# ESP32.net
KiCad netlist of a schematic drawn in EAGLE
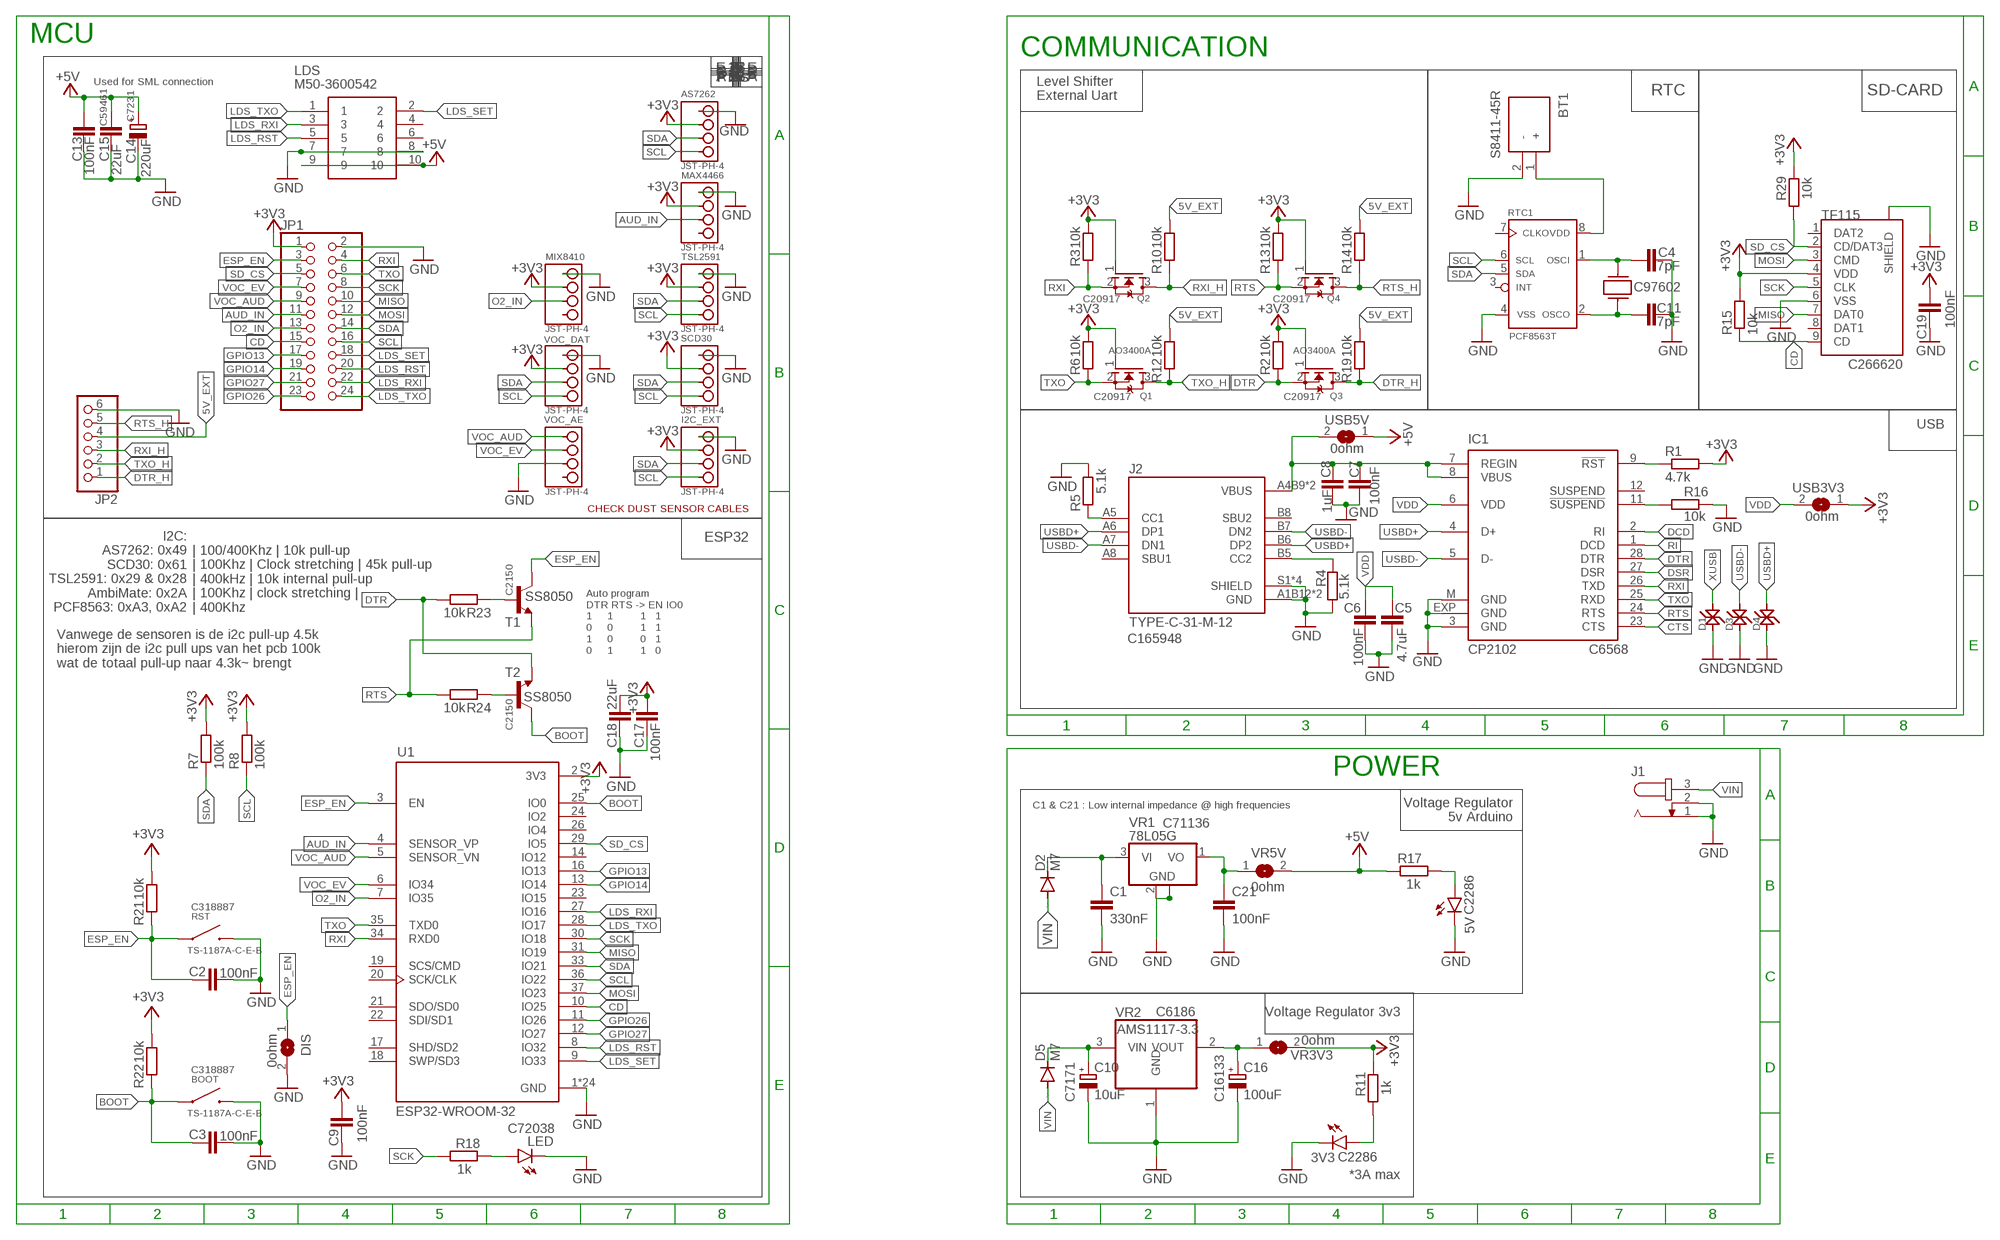
[diagram p0: schematic, sheet 1]

(export (version "E")
  (design (tool "Eeschema 10.0.6"))
  (components
    (comp (ref "3V3")
      (value "C2286")
      (footprint "eagle-import:CHIPLED_0603")
      (fields (field (name "PTNR") "C2286"))
      (libsource (lib "eagle-import") (part "LEDCHIPLED_0603"))
    )
    (comp (ref "5V")
      (value "C2286")
      (footprint "eagle-import:CHIPLED_0603")
      (fields (field (name "PTNR") "C2286"))
      (libsource (lib "eagle-import") (part "LEDCHIPLED_0603"))
    )
    (comp (ref "AS7262")
      (value "JST-PH-4")
      (footprint "eagle-import:JST-PH-4")
      (libsource (lib "eagle-import") (part "JST-PH-4"))
    )
    (comp (ref "BOOT")
      (value "TS-1187A-C-E-B")
      (footprint "eagle-import:TS-1187A-C-E-B")
      (fields (field (name "PRTNR") "C318887"))
      (libsource (lib "eagle-import") (part "TS-1187A-C-E-B"))
    )
    (comp (ref "BT1")
      (value "S8411-45R")
      (footprint "eagle-import:S8411-45R_1")
      (fields (field (name "MOUSER_PART_NUMBER") "855-S8411-45R"))
      (libsource (lib "eagle-import") (part "S8411-45R"))
    )
    (comp (ref "C1")
      (value "330nF")
      (footprint "eagle-import:C0805")
      (libsource (lib "eagle-import") (part "C-EUC0805"))
    )
    (comp (ref "C2")
      (value "100nF")
      (footprint "eagle-import:C0402")
      (libsource (lib "eagle-import") (part "C-EUC0402"))
    )
    (comp (ref "C3")
      (value "100nF")
      (footprint "eagle-import:C0402")
      (libsource (lib "eagle-import") (part "C-EUC0402"))
    )
    (comp (ref "C4")
      (value "7pF")
      (footprint "eagle-import:C0402")
      (libsource (lib "eagle-import") (part "C-EUC0402"))
    )
    (comp (ref "C5")
      (value "4.7uF")
      (footprint "eagle-import:C0402")
      (libsource (lib "eagle-import") (part "C-EUC0402"))
    )
    (comp (ref "C6")
      (value "100nF")
      (footprint "eagle-import:C0402")
      (libsource (lib "eagle-import") (part "C-EUC0402"))
    )
    (comp (ref "C7")
      (value "100nF")
      (footprint "eagle-import:C0402")
      (libsource (lib "eagle-import") (part "C-EUC0402"))
    )
    (comp (ref "C8")
      (value "1uF")
      (footprint "eagle-import:C0402")
      (libsource (lib "eagle-import") (part "C-EUC0402"))
    )
    (comp (ref "C9")
      (value "100nF")
      (footprint "eagle-import:C0402")
      (libsource (lib "eagle-import") (part "C-EUC0402"))
    )
    (comp (ref "C10")
      (value "10uF")
      (footprint "eagle-import:A_3216-18R")
      (fields (field (name "PTRNR") "C7171"))
      (libsource (lib "eagle-import") (part "CPOL-EUA/3216-18R"))
    )
    (comp (ref "C11")
      (value "7pF")
      (footprint "eagle-import:C0402")
      (libsource (lib "eagle-import") (part "C-EUC0402"))
    )
    (comp (ref "C13")
      (value "100nF")
      (footprint "eagle-import:C0402")
      (libsource (lib "eagle-import") (part "C-EUC0402"))
    )
    (comp (ref "C14")
      (value "220uF")
      (footprint "eagle-import:D_7343-31R")
      (fields (field (name "PTRNR") "C7231"))
      (libsource (lib "eagle-import") (part "CPOL-EUD/7343-31R"))
    )
    (comp (ref "C15")
      (value "22uF")
      (footprint "eagle-import:C0603")
      (fields (field (name "PTRNR") "C59461"))
      (libsource (lib "eagle-import") (part "C-EUC0603"))
    )
    (comp (ref "C16")
      (value "100uF")
      (footprint "eagle-import:B_3528-21W")
      (fields (field (name "PTRNR") "C16133"))
      (libsource (lib "eagle-import") (part "CPOL-EUB/3528-21W"))
    )
    (comp (ref "C17")
      (value "100nF")
      (footprint "eagle-import:C0402")
      (libsource (lib "eagle-import") (part "C-EUC0402"))
    )
    (comp (ref "C18")
      (value "22uF")
      (footprint "eagle-import:C0603")
      (libsource (lib "eagle-import") (part "C-EUC0603"))
    )
    (comp (ref "C19")
      (value "100nF")
      (footprint "eagle-import:C0402")
      (libsource (lib "eagle-import") (part "C-EUC0402"))
    )
    (comp (ref "C21")
      (value "100nF")
      (footprint "eagle-import:C0402")
      (libsource (lib "eagle-import") (part "C-EUC0402"))
    )
    (comp (ref "D1")
      (value "LESD5D5.0CT1G")
      (footprint "eagle-import:LESD5D5.0CT1G")
      (libsource (lib "eagle-import") (part "LESD5D5.0CT1G"))
    )
    (comp (ref "D2")
      (value "M7")
      (footprint "eagle-import:DO-214AC")
      (libsource (lib "eagle-import") (part "M7DO-214AC"))
    )
    (comp (ref "D3")
      (value "LESD5D5.0CT1G")
      (footprint "eagle-import:LESD5D5.0CT1G")
      (libsource (lib "eagle-import") (part "LESD5D5.0CT1G"))
    )
    (comp (ref "D4")
      (value "LESD5D5.0CT1G")
      (footprint "eagle-import:LESD5D5.0CT1G")
      (libsource (lib "eagle-import") (part "LESD5D5.0CT1G"))
    )
    (comp (ref "D5")
      (value "M7")
      (footprint "eagle-import:DO-214AC")
      (libsource (lib "eagle-import") (part "M7DO-214AC"))
    )
    (comp (ref "DIS")
      (value "0ohm")
      (footprint "eagle-import:SJ")
      (libsource (lib "eagle-import") (part "SJ"))
    )
    (comp (ref "G1")
      (value "32.768KHZ")
      (footprint "eagle-import:32.768KHZ")
      (fields (field (name "PTRNR") "C97602"))
      (libsource (lib "eagle-import") (part "32.768KHZ"))
    )
    (comp (ref "I2C_EXT")
      (value "JST-PH-4")
      (footprint "eagle-import:JST-PH-4")
      (libsource (lib "eagle-import") (part "JST-PH-4"))
    )
    (comp (ref "IC1")
      (value "CP2102")
      (footprint "eagle-import:MLP28")
      (fields
        (field (name "MF") "FARNELL")
        (field (name "MPN") "CP2102-GM")
        (field (name "PTRNR") "C6568")
        (field (name "PTRNR_1") "C6568")
      )
      (libsource (lib "eagle-import") (part "CP2102"))
    )
    (comp (ref "J1")
      (value "JACK-PLUG1")
      (footprint "eagle-import:SPC4078")
      (libsource (lib "eagle-import") (part "JACK-PLUG1"))
    )
    (comp (ref "J2")
      (value "TYPE-C-31-M-12")
      (footprint "eagle-import:HRO_TYPE-C-31-M-12")
      (fields
        (field (name "MF") "HRO Electronics Co., Ltd.")
        (field (name "PTRNR") "C165948")
        (field (name "PTRNR_1") "C165948")
      )
      (libsource (lib "eagle-import") (part "TYPE-C-31-M-12"))
    )
    (comp (ref "JP1")
      (value "PINHD-2X12")
      (footprint "eagle-import:2X12")
      (libsource (lib "eagle-import") (part "PINHD-2X12"))
    )
    (comp (ref "JP2")
      (value "PINHD-1X6/90")
      (footprint "eagle-import:1X06_90")
      (libsource (lib "eagle-import") (part "PINHD-1X6/90"))
    )
    (comp (ref "LDS")
      (value "M50-3600542")
      (footprint "eagle-import:M503600542")
      (fields (field (name "MOUSER_PART_NUMBER") "855-M50-3600542"))
      (libsource (lib "eagle-import") (part "M50-3600542"))
    )
    (comp (ref "LED")
      (value "YELLOW")
      (footprint "eagle-import:CHIPLED_0603")
      (fields (field (name "PTRNR") "C72038"))
      (libsource (lib "eagle-import") (part "LEDCHIPLED_0603"))
    )
    (comp (ref "MAX4466")
      (value "JST-PH-4")
      (footprint "eagle-import:JST-PH-4")
      (libsource (lib "eagle-import") (part "JST-PH-4"))
    )
    (comp (ref "MIX8410")
      (value "JST-PH-4")
      (footprint "eagle-import:JST-PH-4")
      (libsource (lib "eagle-import") (part "Tilmann_31608911_JST-PH-4"))
    )
    (comp (ref "Q1")
      (value "AO3400A")
      (footprint "eagle-import:SOT23")
      (fields (field (name "PTRNR") "C20917"))
      (libsource (lib "eagle-import") (part "MOSFET-NREFLOW"))
    )
    (comp (ref "Q2")
      (value "AO3400A")
      (footprint "eagle-import:SOT23")
      (fields (field (name "PTRNR") "C20917"))
      (libsource (lib "eagle-import") (part "MOSFET-NREFLOW"))
    )
    (comp (ref "Q3")
      (value "AO3400A")
      (footprint "eagle-import:SOT23")
      (fields (field (name "PTRNR") "C20917"))
      (libsource (lib "eagle-import") (part "MOSFET-NREFLOW"))
    )
    (comp (ref "Q4")
      (value "AO3400A")
      (footprint "eagle-import:SOT23")
      (fields (field (name "PTRNR") "C20917"))
      (libsource (lib "eagle-import") (part "MOSFET-NREFLOW"))
    )
    (comp (ref "R1")
      (value "4.7k")
      (footprint "eagle-import:R0402")
      (libsource (lib "eagle-import") (part "R-EU_R0402"))
    )
    (comp (ref "R2")
      (value "10k")
      (footprint "eagle-import:R0402")
      (libsource (lib "eagle-import") (part "R-EU_R0402"))
    )
    (comp (ref "R3")
      (value "10k")
      (footprint "eagle-import:R0402")
      (libsource (lib "eagle-import") (part "R-EU_R0402"))
    )
    (comp (ref "R4")
      (value "5.1k")
      (footprint "eagle-import:R0402")
      (libsource (lib "eagle-import") (part "R-EU_R0402"))
    )
    (comp (ref "R5")
      (value "5.1k")
      (footprint "eagle-import:R0402")
      (libsource (lib "eagle-import") (part "R-EU_R0402"))
    )
    (comp (ref "R6")
      (value "10k")
      (footprint "eagle-import:R0402")
      (libsource (lib "eagle-import") (part "R-EU_R0402"))
    )
    (comp (ref "R7")
      (value "100k")
      (footprint "eagle-import:R0402")
      (libsource (lib "eagle-import") (part "R-EU_R0402"))
    )
    (comp (ref "R8")
      (value "100k")
      (footprint "eagle-import:R0402")
      (libsource (lib "eagle-import") (part "R-EU_R0402"))
    )
    (comp (ref "R10")
      (value "10k")
      (footprint "eagle-import:R0402")
      (libsource (lib "eagle-import") (part "R-EU_R0402"))
    )
    (comp (ref "R11")
      (value "1k")
      (footprint "eagle-import:R0805")
      (libsource (lib "eagle-import") (part "R-EU_R0805"))
    )
    (comp (ref "R12")
      (value "10k")
      (footprint "eagle-import:R0402")
      (libsource (lib "eagle-import") (part "R-EU_R0402"))
    )
    (comp (ref "R13")
      (value "10k")
      (footprint "eagle-import:R0402")
      (libsource (lib "eagle-import") (part "R-EU_R0402"))
    )
    (comp (ref "R14")
      (value "10k")
      (footprint "eagle-import:R0402")
      (libsource (lib "eagle-import") (part "R-EU_R0402"))
    )
    (comp (ref "R15")
      (value "10k")
      (footprint "eagle-import:R0402")
      (libsource (lib "eagle-import") (part "R-EU_R0402"))
    )
    (comp (ref "R16")
      (value "10k")
      (footprint "eagle-import:R0402")
      (libsource (lib "eagle-import") (part "R-EU_R0402"))
    )
    (comp (ref "R17")
      (value "1k")
      (footprint "eagle-import:R0805")
      (libsource (lib "eagle-import") (part "R-EU_R0805"))
    )
    (comp (ref "R18")
      (value "1k")
      (footprint "eagle-import:R0805")
      (libsource (lib "eagle-import") (part "R-EU_R0805"))
    )
    (comp (ref "R19")
      (value "10k")
      (footprint "eagle-import:R0402")
      (libsource (lib "eagle-import") (part "R-EU_R0402"))
    )
    (comp (ref "R21")
      (value "10k")
      (footprint "eagle-import:R0402")
      (libsource (lib "eagle-import") (part "R-EU_R0402"))
    )
    (comp (ref "R22")
      (value "10k")
      (footprint "eagle-import:R0402")
      (libsource (lib "eagle-import") (part "R-EU_R0402"))
    )
    (comp (ref "R23")
      (value "10k")
      (footprint "eagle-import:R0402")
      (libsource (lib "eagle-import") (part "R-EU_R0402"))
    )
    (comp (ref "R24")
      (value "10k")
      (footprint "eagle-import:R0402")
      (libsource (lib "eagle-import") (part "R-EU_R0402"))
    )
    (comp (ref "R29")
      (value "10k")
      (footprint "eagle-import:R0402")
      (libsource (lib "eagle-import") (part "R-EU_R0402"))
    )
    (comp (ref "RST")
      (value "TS-1187A-C-E-B")
      (footprint "eagle-import:TS-1187A-C-E-B")
      (fields (field (name "PRTNR") "C318887"))
      (libsource (lib "eagle-import") (part "TS-1187A-C-E-B"))
    )
    (comp (ref "RTC1")
      (value "PCF8563T")
      (footprint "eagle-import:SOIC8")
      (libsource (lib "eagle-import") (part "PCF8563T"))
    )
    (comp (ref "SCD30")
      (value "JST-PH-4")
      (footprint "eagle-import:JST-PH-4")
      (libsource (lib "eagle-import") (part "JST-PH-4"))
    )
    (comp (ref "T1")
      (value "SS8050")
      (footprint "eagle-import:SOT23-BEC")
      (fields (field (name "PTNR") "C2150"))
      (libsource (lib "eagle-import") (part "-NPN-SOT23-BECBC808"))
    )
    (comp (ref "T2")
      (value "SS8050")
      (footprint "eagle-import:SOT23-BEC")
      (fields (field (name "PTNR") "C2150"))
      (libsource (lib "eagle-import") (part "-NPN-SOT23-BECBC808"))
    )
    (comp (ref "TF115")
      (value "TF-115")
      (footprint "eagle-import:TF-115")
      (fields (field (name "PTRNR") "C266620"))
      (libsource (lib "eagle-import") (part "TF-115"))
    )
    (comp (ref "TSL2591")
      (value "JST-PH-4")
      (footprint "eagle-import:JST-PH-4")
      (libsource (lib "eagle-import") (part "JST-PH-4"))
    )
    (comp (ref "U1")
      (value "ESP32-WROOM-32")
      (footprint "eagle-import:MODULE_ESP32-WROOM-32")
      (fields (field (name "MF") "Espressif Systems"))
      (libsource (lib "eagle-import") (part "ESP32-WROOM-32"))
    )
    (comp (ref "USB3V3")
      (value "0ohm")
      (footprint "eagle-import:SJ")
      (libsource (lib "eagle-import") (part "SJ"))
    )
    (comp (ref "USB5V")
      (value "0ohm")
      (footprint "eagle-import:SJ")
      (libsource (lib "eagle-import") (part "SJ"))
    )
    (comp (ref "VOC_AE")
      (value "JST-PH-4")
      (footprint "eagle-import:JST-PH-4")
      (libsource (lib "eagle-import") (part "JST-PH-4"))
    )
    (comp (ref "VOC_DAT")
      (value "JST-PH-4")
      (footprint "eagle-import:JST-PH-4")
      (libsource (lib "eagle-import") (part "JST-PH-4"))
    )
    (comp (ref "VR1")
      (value "78L05G")
      (footprint "eagle-import:SOT89")
      (fields (field (name "PTRNR") "C71136"))
      (libsource (lib "eagle-import") (part "78LF05"))
    )
    (comp (ref "VR2")
      (value "AMS1117-3.3")
      (footprint "eagle-import:SOT223")
      (fields (field (name "MPN") "REG1117") (field (name "PTNR") "C6186"))
      (libsource (lib "eagle-import") (part "REG1117"))
    )
    (comp (ref "VR3V3")
      (value "0ohm")
      (footprint "eagle-import:SJ")
      (libsource (lib "eagle-import") (part "SJ"))
    )
    (comp (ref "VR5V")
      (value "0ohm")
      (footprint "eagle-import:SJ")
      (libsource (lib "eagle-import") (part "SJ"))
    )
  )
  (nets
    (net (code "1") (name "+3V3") (class "Default")
      (node (ref "AS7262") (pin "P2") (pinfunction "2_P2") (pintype "bidirectional"))
      (node (ref "C17") (pin "2") (pinfunction "2_2") (pintype "passive"))
      (node (ref "C18") (pin "2") (pinfunction "2_2") (pintype "passive"))
      (node (ref "C19") (pin "2") (pinfunction "2_2") (pintype "passive"))
      (node (ref "C9") (pin "2") (pinfunction "2_2") (pintype "passive"))
      (node (ref "I2C_EXT") (pin "P2") (pinfunction "2_P2") (pintype "bidirectional"))
      (node (ref "JP1") (pin "1") (pinfunction "1_1") (pintype "passive"))
      (node (ref "MAX4466") (pin "P2") (pinfunction "2_P2") (pintype "bidirectional"))
      (node (ref "MIX8410") (pin "P2") (pinfunction "2_P2") (pintype "bidirectional"))
      (node (ref "Q1") (pin "1") (pinfunction "G_1") (pintype "bidirectional"))
      (node (ref "Q2") (pin "1") (pinfunction "G_1") (pintype "bidirectional"))
      (node (ref "Q3") (pin "1") (pinfunction "G_1") (pintype "bidirectional"))
      (node (ref "Q4") (pin "1") (pinfunction "G_1") (pintype "bidirectional"))
      (node (ref "R1") (pin "2") (pinfunction "2_2") (pintype "passive"))
      (node (ref "R11") (pin "2") (pinfunction "2_2") (pintype "passive"))
      (node (ref "R13") (pin "1") (pinfunction "1_1") (pintype "passive"))
      (node (ref "R15") (pin "2") (pinfunction "2_2") (pintype "passive"))
      (node (ref "R2") (pin "1") (pinfunction "1_1") (pintype "passive"))
      (node (ref "R21") (pin "1") (pinfunction "1_1") (pintype "passive"))
      (node (ref "R22") (pin "1") (pinfunction "1_1") (pintype "passive"))
      (node (ref "R29") (pin "2") (pinfunction "2_2") (pintype "passive"))
      (node (ref "R3") (pin "1") (pinfunction "1_1") (pintype "passive"))
      (node (ref "R6") (pin "1") (pinfunction "1_1") (pintype "passive"))
      (node (ref "R7") (pin "2") (pinfunction "2_2") (pintype "passive"))
      (node (ref "R8") (pin "2") (pinfunction "2_2") (pintype "passive"))
      (node (ref "SCD30") (pin "P2") (pinfunction "2_P2") (pintype "bidirectional"))
      (node (ref "TF115") (pin "4") (pinfunction "VDD_4") (pintype "bidirectional"))
      (node (ref "TSL2591") (pin "P2") (pinfunction "2_P2") (pintype "bidirectional"))
      (node (ref "U1") (pin "2") (pinfunction "3V3_2") (pintype "power_in"))
      (node (ref "USB3V3") (pin "1") (pinfunction "1_1") (pintype "passive"))
      (node (ref "VOC_DAT") (pin "P2") (pinfunction "2_P2") (pintype "bidirectional"))
      (node (ref "VR3V3") (pin "2") (pinfunction "2_2") (pintype "passive"))
    )
    (net (code "2") (name "+5V") (class "Default")
      (node (ref "C13") (pin "1") (pinfunction "1_1") (pintype "passive"))
      (node (ref "C14") (pin "+") (pinfunction "+_+") (pintype "passive"))
      (node (ref "C15") (pin "1") (pinfunction "1_1") (pintype "passive"))
      (node (ref "LDS") (pin "10") (pinfunction "10_10") (pintype "bidirectional"))
      (node (ref "LDS") (pin "9") (pinfunction "9_9") (pintype "bidirectional"))
      (node (ref "R17") (pin "2") (pinfunction "2_2") (pintype "passive"))
      (node (ref "USB5V") (pin "1") (pinfunction "1_1") (pintype "passive"))
      (node (ref "VR5V") (pin "2") (pinfunction "2_2") (pintype "passive"))
    )
    (net (code "3") (name "5V_EXT") (class "Default")
      (node (ref "JP2") (pin "4") (pinfunction "4_4") (pintype "passive"))
      (node (ref "R10") (pin "1") (pinfunction "1_1") (pintype "passive"))
      (node (ref "R12") (pin "1") (pinfunction "1_1") (pintype "passive"))
      (node (ref "R14") (pin "1") (pinfunction "1_1") (pintype "passive"))
      (node (ref "R19") (pin "1") (pinfunction "1_1") (pintype "passive"))
    )
    (net (code "4") (name "AUD_IN") (class "Default")
      (node (ref "JP1") (pin "11") (pinfunction "11_11") (pintype "passive"))
      (node (ref "MAX4466") (pin "P3") (pinfunction "3_P3") (pintype "bidirectional"))
      (node (ref "U1") (pin "4") (pinfunction "SENSOR_VP_4") (pintype "input"))
    )
    (net (code "5") (name "BOOT") (class "Default")
      (node (ref "BOOT") (pin "A") (pinfunction "A_A") (pintype "bidirectional"))
      (node (ref "BOOT") (pin "B") (pinfunction "A_B") (pintype "bidirectional"))
      (node (ref "C3") (pin "1") (pinfunction "1_1") (pintype "passive"))
      (node (ref "R22") (pin "2") (pinfunction "2_2") (pintype "passive"))
      (node (ref "T2") (pin "C") (pinfunction "C_C") (pintype "passive"))
      (node (ref "U1") (pin "25") (pinfunction "IO0_25") (pintype "bidirectional"))
    )
    (net (code "6") (name "CD") (class "Default")
      (node (ref "JP1") (pin "15") (pinfunction "15_15") (pintype "passive"))
      (node (ref "R15") (pin "1") (pinfunction "1_1") (pintype "passive"))
      (node (ref "TF115") (pin "9") (pinfunction "CD_9") (pintype "bidirectional"))
      (node (ref "U1") (pin "10") (pinfunction "IO25_10") (pintype "bidirectional"))
    )
    (net (code "7") (name "CTS") (class "Default")
      (node (ref "IC1") (pin "23") (pinfunction "CTS_23") (pintype "input"))
    )
    (net (code "8") (name "DCD") (class "Default")
      (node (ref "IC1") (pin "2") (pinfunction "RI_2") (pintype "input"))
    )
    (net (code "9") (name "DSR") (class "Default")
      (node (ref "IC1") (pin "27") (pinfunction "DSR_27") (pintype "input"))
    )
    (net (code "10") (name "DTR") (class "Default")
      (node (ref "IC1") (pin "28") (pinfunction "DTR_28") (pintype "output"))
      (node (ref "Q3") (pin "2") (pinfunction "S_2") (pintype "bidirectional"))
      (node (ref "R2") (pin "2") (pinfunction "2_2") (pintype "passive"))
      (node (ref "R23") (pin "1") (pinfunction "1_1") (pintype "passive"))
      (node (ref "T2") (pin "E") (pinfunction "E_E") (pintype "passive"))
    )
    (net (code "11") (name "DTR_H") (class "Default")
      (node (ref "JP2") (pin "1") (pinfunction "1_1") (pintype "passive"))
      (node (ref "Q3") (pin "3") (pinfunction "D_3") (pintype "bidirectional"))
      (node (ref "R19") (pin "2") (pinfunction "2_2") (pintype "passive"))
    )
    (net (code "12") (name "ESP_EN") (class "Default")
      (node (ref "C2") (pin "1") (pinfunction "1_1") (pintype "passive"))
      (node (ref "DIS") (pin "1") (pinfunction "1_1") (pintype "passive"))
      (node (ref "JP1") (pin "3") (pinfunction "3_3") (pintype "passive"))
      (node (ref "R21") (pin "2") (pinfunction "2_2") (pintype "passive"))
      (node (ref "RST") (pin "A") (pinfunction "A_A") (pintype "bidirectional"))
      (node (ref "RST") (pin "B") (pinfunction "A_B") (pintype "bidirectional"))
      (node (ref "T1") (pin "C") (pinfunction "C_C") (pintype "passive"))
      (node (ref "U1") (pin "3") (pinfunction "EN_3") (pintype "input"))
    )
    (net (code "13") (name "GND") (class "Default")
      (node (ref "3V3") (pin "C") (pinfunction "C_C") (pintype "passive"))
      (node (ref "5V") (pin "C") (pinfunction "C_C") (pintype "passive"))
      (node (ref "AS7262") (pin "P1") (pinfunction "1_P1") (pintype "bidirectional"))
      (node (ref "BOOT") (pin "C") (pinfunction "C_C") (pintype "bidirectional"))
      (node (ref "BOOT") (pin "D") (pinfunction "C_D") (pintype "bidirectional"))
      (node (ref "BT1") (pin "2") (pinfunction "-_2") (pintype "bidirectional"))
      (node (ref "C1") (pin "2") (pinfunction "2_2") (pintype "passive"))
      (node (ref "C10") (pin "-") (pinfunction "-_-") (pintype "passive"))
      (node (ref "C11") (pin "2") (pinfunction "2_2") (pintype "passive"))
      (node (ref "C13") (pin "2") (pinfunction "2_2") (pintype "passive"))
      (node (ref "C14") (pin "-") (pinfunction "-_-") (pintype "passive"))
      (node (ref "C15") (pin "2") (pinfunction "2_2") (pintype "passive"))
      (node (ref "C16") (pin "-") (pinfunction "-_-") (pintype "passive"))
      (node (ref "C17") (pin "1") (pinfunction "1_1") (pintype "passive"))
      (node (ref "C18") (pin "1") (pinfunction "1_1") (pintype "passive"))
      (node (ref "C19") (pin "1") (pinfunction "1_1") (pintype "passive"))
      (node (ref "C2") (pin "2") (pinfunction "2_2") (pintype "passive"))
      (node (ref "C21") (pin "2") (pinfunction "2_2") (pintype "passive"))
      (node (ref "C3") (pin "2") (pinfunction "2_2") (pintype "passive"))
      (node (ref "C4") (pin "2") (pinfunction "2_2") (pintype "passive"))
      (node (ref "C5") (pin "2") (pinfunction "2_2") (pintype "passive"))
      (node (ref "C6") (pin "2") (pinfunction "2_2") (pintype "passive"))
      (node (ref "C7") (pin "2") (pinfunction "2_2") (pintype "passive"))
      (node (ref "C8") (pin "2") (pinfunction "2_2") (pintype "passive"))
      (node (ref "C9") (pin "1") (pinfunction "1_1") (pintype "passive"))
      (node (ref "D1") (pin "P$1") (pinfunction "P$1_P$1") (pintype "bidirectional"))
      (node (ref "D3") (pin "P$1") (pinfunction "P$1_P$1") (pintype "bidirectional"))
      (node (ref "D4") (pin "P$1") (pinfunction "P$1_P$1") (pintype "bidirectional"))
      (node (ref "DIS") (pin "2") (pinfunction "2_2") (pintype "passive"))
      (node (ref "I2C_EXT") (pin "P1") (pinfunction "1_P1") (pintype "bidirectional"))
      (node (ref "IC1") (pin "3") (pinfunction "GND_3") (pintype "power_in"))
      (node (ref "IC1") (pin "EXP") (pinfunction "GND_EXP") (pintype "power_in"))
      (node (ref "IC1") (pin "M") (pinfunction "GND_M") (pintype "power_in"))
      (node (ref "J1") (pin "1") (pinfunction "1_1") (pintype "passive"))
      (node (ref "J1") (pin "2") (pinfunction "2_2") (pintype "passive"))
      (node (ref "J2") (pin "A1B12") (pinfunction "GND_A1B12") (pintype "power_in"))
      (node (ref "J2") (pin "B1A12") (pinfunction "GND_B1A12") (pintype "power_in"))
      (node (ref "J2") (pin "S1") (pinfunction "SHIELD_S1") (pintype "passive"))
      (node (ref "J2") (pin "S2") (pinfunction "SHIELD_S2") (pintype "passive"))
      (node (ref "J2") (pin "S3") (pinfunction "SHIELD_S3") (pintype "passive"))
      (node (ref "J2") (pin "S4") (pinfunction "SHIELD_S4") (pintype "passive"))
      (node (ref "JP1") (pin "2") (pinfunction "2_2") (pintype "passive"))
      (node (ref "JP2") (pin "6") (pinfunction "6_6") (pintype "passive"))
      (node (ref "LDS") (pin "7") (pinfunction "7_7") (pintype "bidirectional"))
      (node (ref "LDS") (pin "8") (pinfunction "8_8") (pintype "bidirectional"))
      (node (ref "LED") (pin "C") (pinfunction "C_C") (pintype "passive"))
      (node (ref "MAX4466") (pin "P1") (pinfunction "1_P1") (pintype "bidirectional"))
      (node (ref "MIX8410") (pin "P1") (pinfunction "1_P1") (pintype "bidirectional"))
      (node (ref "R16") (pin "1") (pinfunction "1_1") (pintype "passive"))
      (node (ref "R4") (pin "2") (pinfunction "2_2") (pintype "passive"))
      (node (ref "R5") (pin "2") (pinfunction "2_2") (pintype "passive"))
      (node (ref "RST") (pin "C") (pinfunction "C_C") (pintype "bidirectional"))
      (node (ref "RST") (pin "D") (pinfunction "C_D") (pintype "bidirectional"))
      (node (ref "RTC1") (pin "4") (pinfunction "VSS_4") (pintype "bidirectional"))
      (node (ref "SCD30") (pin "P1") (pinfunction "1_P1") (pintype "bidirectional"))
      (node (ref "TF115") (pin "10") (pinfunction "SHIELD_10") (pintype "bidirectional"))
      (node (ref "TF115") (pin "11") (pinfunction "SHIELD_11") (pintype "bidirectional"))
      (node (ref "TF115") (pin "12") (pinfunction "SHIELD_12") (pintype "bidirectional"))
      (node (ref "TF115") (pin "13") (pinfunction "SHIELD_13") (pintype "bidirectional"))
      (node (ref "TF115") (pin "6") (pinfunction "VSS_6") (pintype "bidirectional"))
      (node (ref "TSL2591") (pin "P1") (pinfunction "1_P1") (pintype "bidirectional"))
      (node (ref "U1") (pin "1") (pinfunction "GND_1") (pintype "power_in"))
      (node (ref "U1") (pin "15") (pinfunction "GND_15") (pintype "power_in"))
      (node (ref "U1") (pin "38") (pinfunction "GND_38") (pintype "power_in"))
      (node (ref "U1") (pin "39_1") (pinfunction "GND_39_1") (pintype "power_in"))
      (node (ref "U1") (pin "39_10") (pinfunction "GND_39_10") (pintype "power_in"))
      (node (ref "U1") (pin "39_11") (pinfunction "GND_39_11") (pintype "power_in"))
      (node (ref "U1") (pin "39_12") (pinfunction "GND_39_12") (pintype "power_in"))
      (node (ref "U1") (pin "39_13") (pinfunction "GND_39_13") (pintype "power_in"))
      (node (ref "U1") (pin "39_14") (pinfunction "GND_39_14") (pintype "power_in"))
      (node (ref "U1") (pin "39_15") (pinfunction "GND_39_15") (pintype "power_in"))
      (node (ref "U1") (pin "39_16") (pinfunction "GND_39_16") (pintype "power_in"))
      (node (ref "U1") (pin "39_17") (pinfunction "GND_39_17") (pintype "power_in"))
      (node (ref "U1") (pin "39_18") (pinfunction "GND_39_18") (pintype "power_in"))
      (node (ref "U1") (pin "39_19") (pinfunction "GND_39_19") (pintype "power_in"))
      (node (ref "U1") (pin "39_2") (pinfunction "GND_39_2") (pintype "power_in"))
      (node (ref "U1") (pin "39_20") (pinfunction "GND_39_20") (pintype "power_in"))
      (node (ref "U1") (pin "39_21") (pinfunction "GND_39_21") (pintype "power_in"))
      (node (ref "U1") (pin "39_3") (pinfunction "GND_39_3") (pintype "power_in"))
      (node (ref "U1") (pin "39_4") (pinfunction "GND_39_4") (pintype "power_in"))
      (node (ref "U1") (pin "39_5") (pinfunction "GND_39_5") (pintype "power_in"))
      (node (ref "U1") (pin "39_6") (pinfunction "GND_39_6") (pintype "power_in"))
      (node (ref "U1") (pin "39_7") (pinfunction "GND_39_7") (pintype "power_in"))
      (node (ref "U1") (pin "39_8") (pinfunction "GND_39_8") (pintype "power_in"))
      (node (ref "U1") (pin "39_9") (pinfunction "GND_39_9") (pintype "power_in"))
      (node (ref "VOC_AE") (pin "P3") (pinfunction "3_P3") (pintype "bidirectional"))
      (node (ref "VOC_DAT") (pin "P1") (pinfunction "1_P1") (pintype "bidirectional"))
      (node (ref "VR1") (pin "2") (pinfunction "GND_2") (pintype "passive"))
      (node (ref "VR1") (pin "2@1") (pinfunction "GND_2@1") (pintype "passive"))
      (node (ref "VR2") (pin "1") (pinfunction "GND_1") (pintype "power_in"))
    )
    (net (code "14") (name "GPIO13") (class "Default")
      (node (ref "JP1") (pin "17") (pinfunction "17_17") (pintype "passive"))
      (node (ref "U1") (pin "16") (pinfunction "IO13_16") (pintype "bidirectional"))
    )
    (net (code "15") (name "GPIO14") (class "Default")
      (node (ref "JP1") (pin "19") (pinfunction "19_19") (pintype "passive"))
      (node (ref "U1") (pin "13") (pinfunction "IO14_13") (pintype "bidirectional"))
    )
    (net (code "16") (name "GPIO26") (class "Default")
      (node (ref "JP1") (pin "23") (pinfunction "23_23") (pintype "passive"))
      (node (ref "U1") (pin "11") (pinfunction "IO26_11") (pintype "bidirectional"))
    )
    (net (code "17") (name "GPIO27") (class "Default")
      (node (ref "JP1") (pin "21") (pinfunction "21_21") (pintype "passive"))
      (node (ref "U1") (pin "12") (pinfunction "IO27_12") (pintype "bidirectional"))
    )
    (net (code "18") (name "LDS_RST") (class "Default")
      (node (ref "JP1") (pin "20") (pinfunction "20_20") (pintype "passive"))
      (node (ref "LDS") (pin "5") (pinfunction "5_5") (pintype "bidirectional"))
      (node (ref "U1") (pin "8") (pinfunction "IO32_8") (pintype "bidirectional"))
    )
    (net (code "19") (name "LDS_RXI") (class "Default")
      (node (ref "JP1") (pin "22") (pinfunction "22_22") (pintype "passive"))
      (node (ref "LDS") (pin "3") (pinfunction "3_3") (pintype "bidirectional"))
      (node (ref "U1") (pin "27") (pinfunction "IO16_27") (pintype "bidirectional"))
    )
    (net (code "20") (name "LDS_SET") (class "Default")
      (node (ref "JP1") (pin "18") (pinfunction "18_18") (pintype "passive"))
      (node (ref "LDS") (pin "2") (pinfunction "2_2") (pintype "bidirectional"))
      (node (ref "U1") (pin "9") (pinfunction "IO33_9") (pintype "bidirectional"))
    )
    (net (code "21") (name "LDS_TXO") (class "Default")
      (node (ref "JP1") (pin "24") (pinfunction "24_24") (pintype "passive"))
      (node (ref "LDS") (pin "1") (pinfunction "1_1") (pintype "bidirectional"))
      (node (ref "U1") (pin "28") (pinfunction "IO17_28") (pintype "bidirectional"))
    )
    (net (code "22") (name "MISO") (class "Default")
      (node (ref "JP1") (pin "10") (pinfunction "10_10") (pintype "passive"))
      (node (ref "TF115") (pin "7") (pinfunction "DAT0_7") (pintype "bidirectional"))
      (node (ref "U1") (pin "31") (pinfunction "IO19_31") (pintype "bidirectional"))
    )
    (net (code "23") (name "MOSI") (class "Default")
      (node (ref "JP1") (pin "12") (pinfunction "12_12") (pintype "passive"))
      (node (ref "TF115") (pin "3") (pinfunction "CMD_3") (pintype "bidirectional"))
      (node (ref "U1") (pin "37") (pinfunction "IO23_37") (pintype "bidirectional"))
    )
    (net (code "24") (name "Net-(3V3-PadA)") (class "Default")
      (node (ref "3V3") (pin "A") (pinfunction "A_A") (pintype "passive"))
      (node (ref "R11") (pin "1") (pinfunction "1_1") (pintype "passive"))
    )
    (net (code "25") (name "Net-(5V-PadA)") (class "Default")
      (node (ref "5V") (pin "A") (pinfunction "A_A") (pintype "passive"))
      (node (ref "R17") (pin "1") (pinfunction "1_1") (pintype "passive"))
    )
    (net (code "26") (name "Net-(BT1-+)") (class "Default")
      (node (ref "BT1") (pin "1") (pinfunction "+_1") (pintype "bidirectional"))
      (node (ref "RTC1") (pin "8") (pinfunction "VDD_8") (pintype "bidirectional"))
    )
    (net (code "27") (name "Net-(IC1-~{RST})") (class "Default")
      (node (ref "IC1") (pin "9") (pinfunction "~{RST}_9") (pintype "bidirectional"))
      (node (ref "R1") (pin "1") (pinfunction "1_1") (pintype "passive"))
    )
    (net (code "28") (name "Net-(IC1-~{SUSPEND})") (class "Default")
      (node (ref "IC1") (pin "11") (pinfunction "~{SUSPEND}_11") (pintype "output"))
      (node (ref "R16") (pin "2") (pinfunction "2_2") (pintype "passive"))
    )
    (net (code "29") (name "Net-(J2-CC1)") (class "Default")
      (node (ref "J2") (pin "A5") (pinfunction "CC1_A5") (pintype "bidirectional"))
      (node (ref "R5") (pin "1") (pinfunction "1_1") (pintype "passive"))
    )
    (net (code "30") (name "Net-(J2-CC2)") (class "Default")
      (node (ref "J2") (pin "B5") (pinfunction "CC2_B5") (pintype "bidirectional"))
      (node (ref "R4") (pin "1") (pinfunction "1_1") (pintype "passive"))
    )
    (net (code "31") (name "Net-(LED-PadA)") (class "Default")
      (node (ref "LED") (pin "A") (pinfunction "A_A") (pintype "passive"))
      (node (ref "R18") (pin "2") (pinfunction "2_2") (pintype "passive"))
    )
    (net (code "32") (name "Net-(R23-Pad2)") (class "Default")
      (node (ref "R23") (pin "2") (pinfunction "2_2") (pintype "passive"))
      (node (ref "T1") (pin "B") (pinfunction "B_B") (pintype "passive"))
    )
    (net (code "33") (name "Net-(R24-Pad2)") (class "Default")
      (node (ref "R24") (pin "2") (pinfunction "2_2") (pintype "passive"))
      (node (ref "T2") (pin "B") (pinfunction "B_B") (pintype "passive"))
    )
    (net (code "34") (name "Net-(RTC1-OSCI)") (class "Default")
      (node (ref "C4") (pin "1") (pinfunction "1_1") (pintype "passive"))
      (node (ref "G1") (pin "2") (pinfunction "2_2") (pintype "bidirectional"))
      (node (ref "RTC1") (pin "1") (pinfunction "OSCI_1") (pintype "bidirectional"))
    )
    (net (code "35") (name "Net-(RTC1-OSCO)") (class "Default")
      (node (ref "C11") (pin "1") (pinfunction "1_1") (pintype "passive"))
      (node (ref "G1") (pin "1") (pinfunction "1_1") (pintype "bidirectional"))
      (node (ref "RTC1") (pin "2") (pinfunction "OSCO_2") (pintype "bidirectional"))
    )
    (net (code "36") (name "Net-(VR1-VI)") (class "Default")
      (node (ref "C1") (pin "1") (pinfunction "1_1") (pintype "passive"))
      (node (ref "D2") (pin "C") (pinfunction "C_C") (pintype "passive"))
      (node (ref "VR1") (pin "3") (pinfunction "VI_3") (pintype "input"))
    )
    (net (code "37") (name "Net-(VR1-VO)") (class "Default")
      (node (ref "C21") (pin "1") (pinfunction "1_1") (pintype "passive"))
      (node (ref "VR1") (pin "1") (pinfunction "VO_1") (pintype "passive"))
      (node (ref "VR5V") (pin "1") (pinfunction "1_1") (pintype "passive"))
    )
    (net (code "38") (name "Net-(VR2-VIN)") (class "Default")
      (node (ref "C10") (pin "+") (pinfunction "+_+") (pintype "passive"))
      (node (ref "D5") (pin "C") (pinfunction "C_C") (pintype "passive"))
      (node (ref "VR2") (pin "3") (pinfunction "VIN_3") (pintype "input"))
    )
    (net (code "39") (name "Net-(VR2-VOUT)") (class "Default")
      (node (ref "C16") (pin "+") (pinfunction "+_+") (pintype "passive"))
      (node (ref "VR2") (pin "2") (pinfunction "VOUT_2") (pintype "output"))
      (node (ref "VR3V3") (pin "1") (pinfunction "1_1") (pintype "passive"))
    )
    (net (code "40") (name "O2_IN") (class "Default")
      (node (ref "JP1") (pin "13") (pinfunction "13_13") (pintype "passive"))
      (node (ref "MIX8410") (pin "P3") (pinfunction "3_P3") (pintype "bidirectional"))
      (node (ref "U1") (pin "7") (pinfunction "IO35_7") (pintype "input"))
    )
    (net (code "41") (name "RI") (class "Default")
      (node (ref "IC1") (pin "1") (pinfunction "DCD_1") (pintype "input"))
    )
    (net (code "42") (name "RTS") (class "Default")
      (node (ref "IC1") (pin "24") (pinfunction "RTS_24") (pintype "output"))
      (node (ref "Q4") (pin "2") (pinfunction "S_2") (pintype "bidirectional"))
      (node (ref "R13") (pin "2") (pinfunction "2_2") (pintype "passive"))
      (node (ref "R24") (pin "1") (pinfunction "1_1") (pintype "passive"))
      (node (ref "T1") (pin "E") (pinfunction "E_E") (pintype "passive"))
    )
    (net (code "43") (name "RTS_H") (class "Default")
      (node (ref "JP2") (pin "5") (pinfunction "5_5") (pintype "passive"))
      (node (ref "Q4") (pin "3") (pinfunction "D_3") (pintype "bidirectional"))
      (node (ref "R14") (pin "2") (pinfunction "2_2") (pintype "passive"))
    )
    (net (code "44") (name "RXI") (class "Default")
      (node (ref "IC1") (pin "26") (pinfunction "TXD_26") (pintype "output"))
      (node (ref "JP1") (pin "4") (pinfunction "4_4") (pintype "passive"))
      (node (ref "Q2") (pin "2") (pinfunction "S_2") (pintype "bidirectional"))
      (node (ref "R3") (pin "2") (pinfunction "2_2") (pintype "passive"))
      (node (ref "U1") (pin "34") (pinfunction "RXD0_34") (pintype "bidirectional"))
    )
    (net (code "45") (name "RXI_H") (class "Default")
      (node (ref "JP2") (pin "3") (pinfunction "3_3") (pintype "passive"))
      (node (ref "Q2") (pin "3") (pinfunction "D_3") (pintype "bidirectional"))
      (node (ref "R10") (pin "2") (pinfunction "2_2") (pintype "passive"))
    )
    (net (code "46") (name "SCK") (class "Default")
      (node (ref "JP1") (pin "8") (pinfunction "8_8") (pintype "passive"))
      (node (ref "R18") (pin "1") (pinfunction "1_1") (pintype "passive"))
      (node (ref "TF115") (pin "5") (pinfunction "CLK_5") (pintype "bidirectional"))
      (node (ref "U1") (pin "30") (pinfunction "IO18_30") (pintype "bidirectional"))
    )
    (net (code "47") (name "SCL") (class "Default")
      (node (ref "AS7262") (pin "P4") (pinfunction "4_P4") (pintype "bidirectional"))
      (node (ref "I2C_EXT") (pin "P4") (pinfunction "4_P4") (pintype "bidirectional"))
      (node (ref "JP1") (pin "16") (pinfunction "16_16") (pintype "passive"))
      (node (ref "R8") (pin "1") (pinfunction "1_1") (pintype "passive"))
      (node (ref "RTC1") (pin "6") (pinfunction "SCL_6") (pintype "bidirectional"))
      (node (ref "SCD30") (pin "P4") (pinfunction "4_P4") (pintype "bidirectional"))
      (node (ref "TSL2591") (pin "P4") (pinfunction "4_P4") (pintype "bidirectional"))
      (node (ref "U1") (pin "36") (pinfunction "IO22_36") (pintype "bidirectional"))
      (node (ref "VOC_DAT") (pin "P4") (pinfunction "4_P4") (pintype "bidirectional"))
    )
    (net (code "48") (name "SDA") (class "Default")
      (node (ref "AS7262") (pin "P3") (pinfunction "3_P3") (pintype "bidirectional"))
      (node (ref "I2C_EXT") (pin "P3") (pinfunction "3_P3") (pintype "bidirectional"))
      (node (ref "JP1") (pin "14") (pinfunction "14_14") (pintype "passive"))
      (node (ref "R7") (pin "1") (pinfunction "1_1") (pintype "passive"))
      (node (ref "RTC1") (pin "5") (pinfunction "SDA_5") (pintype "bidirectional"))
      (node (ref "SCD30") (pin "P3") (pinfunction "3_P3") (pintype "bidirectional"))
      (node (ref "TSL2591") (pin "P3") (pinfunction "3_P3") (pintype "bidirectional"))
      (node (ref "U1") (pin "33") (pinfunction "IO21_33") (pintype "bidirectional"))
      (node (ref "VOC_DAT") (pin "P3") (pinfunction "3_P3") (pintype "bidirectional"))
    )
    (net (code "49") (name "SD_CS") (class "Default")
      (node (ref "JP1") (pin "5") (pinfunction "5_5") (pintype "passive"))
      (node (ref "R29") (pin "1") (pinfunction "1_1") (pintype "passive"))
      (node (ref "TF115") (pin "2") (pinfunction "CD/DAT3_2") (pintype "bidirectional"))
      (node (ref "U1") (pin "29") (pinfunction "IO5_29") (pintype "bidirectional"))
    )
    (net (code "50") (name "TXO") (class "Default")
      (node (ref "IC1") (pin "25") (pinfunction "RXD_25") (pintype "input"))
      (node (ref "JP1") (pin "6") (pinfunction "6_6") (pintype "passive"))
      (node (ref "Q1") (pin "2") (pinfunction "S_2") (pintype "bidirectional"))
      (node (ref "R6") (pin "2") (pinfunction "2_2") (pintype "passive"))
      (node (ref "U1") (pin "35") (pinfunction "TXD0_35") (pintype "bidirectional"))
    )
    (net (code "51") (name "TXO_H") (class "Default")
      (node (ref "JP2") (pin "2") (pinfunction "2_2") (pintype "passive"))
      (node (ref "Q1") (pin "3") (pinfunction "D_3") (pintype "bidirectional"))
      (node (ref "R12") (pin "2") (pinfunction "2_2") (pintype "passive"))
    )
    (net (code "52") (name "USBD+") (class "Default")
      (node (ref "D4") (pin "P$2") (pinfunction "P$2_P$2") (pintype "bidirectional"))
      (node (ref "IC1") (pin "4") (pinfunction "D+_4") (pintype "bidirectional"))
      (node (ref "J2") (pin "A6") (pinfunction "DP1_A6") (pintype "bidirectional"))
      (node (ref "J2") (pin "B6") (pinfunction "DP2_B6") (pintype "bidirectional"))
    )
    (net (code "53") (name "USBD-") (class "Default")
      (node (ref "D3") (pin "P$2") (pinfunction "P$2_P$2") (pintype "bidirectional"))
      (node (ref "IC1") (pin "5") (pinfunction "D-_5") (pintype "bidirectional"))
      (node (ref "J2") (pin "A7") (pinfunction "DN1_A7") (pintype "bidirectional"))
      (node (ref "J2") (pin "B7") (pinfunction "DN2_B7") (pintype "bidirectional"))
    )
    (net (code "54") (name "VDD") (class "Default")
      (node (ref "C5") (pin "1") (pinfunction "1_1") (pintype "passive"))
      (node (ref "C6") (pin "1") (pinfunction "1_1") (pintype "passive"))
      (node (ref "IC1") (pin "6") (pinfunction "VDD_6") (pintype "power_in"))
      (node (ref "USB3V3") (pin "2") (pinfunction "2_2") (pintype "passive"))
    )
    (net (code "55") (name "VIN") (class "Default")
      (node (ref "D2") (pin "A") (pinfunction "A_A") (pintype "passive"))
      (node (ref "D5") (pin "A") (pinfunction "A_A") (pintype "passive"))
      (node (ref "J1") (pin "3") (pinfunction "3_3") (pintype "passive"))
    )
    (net (code "56") (name "VOC_AUD") (class "Default")
      (node (ref "JP1") (pin "9") (pinfunction "9_9") (pintype "passive"))
      (node (ref "U1") (pin "5") (pinfunction "SENSOR_VN_5") (pintype "input"))
      (node (ref "VOC_AE") (pin "P1") (pinfunction "1_P1") (pintype "bidirectional"))
    )
    (net (code "57") (name "VOC_EV") (class "Default")
      (node (ref "JP1") (pin "7") (pinfunction "7_7") (pintype "passive"))
      (node (ref "U1") (pin "6") (pinfunction "IO34_6") (pintype "input"))
      (node (ref "VOC_AE") (pin "P2") (pinfunction "2_P2") (pintype "bidirectional"))
    )
    (net (code "58") (name "XUSB") (class "Default")
      (node (ref "C7") (pin "1") (pinfunction "1_1") (pintype "passive"))
      (node (ref "C8") (pin "1") (pinfunction "1_1") (pintype "passive"))
      (node (ref "D1") (pin "P$2") (pinfunction "P$2_P$2") (pintype "bidirectional"))
      (node (ref "IC1") (pin "7") (pinfunction "REGIN_7") (pintype "passive"))
      (node (ref "IC1") (pin "8") (pinfunction "VBUS_8") (pintype "input"))
      (node (ref "J2") (pin "A4B9") (pinfunction "VBUS_A4B9") (pintype "power_in"))
      (node (ref "J2") (pin "B4A9") (pinfunction "VBUS_B4A9") (pintype "power_in"))
      (node (ref "USB5V") (pin "2") (pinfunction "2_2") (pintype "passive"))
    )
    (net (code "59") (name "unconnected-(IC1-SUSPEND-Pad12)") (class "Default")
      (node (ref "IC1") (pin "12") (pinfunction "SUSPEND_12") (pintype "output"))
    )
    (net (code "60") (name "unconnected-(J2-SBU1-PadA8)") (class "Default")
      (node (ref "J2") (pin "A8") (pinfunction "SBU1_A8") (pintype "bidirectional"))
    )
    (net (code "61") (name "unconnected-(J2-SBU2-PadB8)") (class "Default")
      (node (ref "J2") (pin "B8") (pinfunction "SBU2_B8") (pintype "bidirectional"))
    )
    (net (code "62") (name "unconnected-(LDS-Pad4)") (class "Default")
      (node (ref "LDS") (pin "4") (pinfunction "4_4") (pintype "bidirectional"))
    )
    (net (code "63") (name "unconnected-(LDS-Pad6)") (class "Default")
      (node (ref "LDS") (pin "6") (pinfunction "6_6") (pintype "bidirectional"))
    )
    (net (code "64") (name "unconnected-(MAX4466-4-PadP4)") (class "Default")
      (node (ref "MAX4466") (pin "P4") (pinfunction "4_P4") (pintype "bidirectional"))
    )
    (net (code "65") (name "unconnected-(MIX8410-4-PadP4)") (class "Default")
      (node (ref "MIX8410") (pin "P4") (pinfunction "4_P4") (pintype "bidirectional"))
    )
    (net (code "66") (name "unconnected-(RTC1-CLKO-Pad7)") (class "Default")
      (node (ref "RTC1") (pin "7") (pinfunction "CLKO_7") (pintype "bidirectional"))
    )
    (net (code "67") (name "unconnected-(RTC1-{slash}INT-Pad3)") (class "Default")
      (node (ref "RTC1") (pin "3") (pinfunction "/INT_3") (pintype "bidirectional"))
    )
    (net (code "68") (name "unconnected-(TF115-DAT1-Pad8)") (class "Default")
      (node (ref "TF115") (pin "8") (pinfunction "DAT1_8") (pintype "bidirectional"))
    )
    (net (code "69") (name "unconnected-(TF115-DAT2-Pad1)") (class "Default")
      (node (ref "TF115") (pin "1") (pinfunction "DAT2_1") (pintype "bidirectional"))
    )
    (net (code "70") (name "unconnected-(U1-IO2-Pad24)") (class "Default")
      (node (ref "U1") (pin "24") (pinfunction "IO2_24") (pintype "bidirectional"))
    )
    (net (code "71") (name "unconnected-(U1-IO4-Pad26)") (class "Default")
      (node (ref "U1") (pin "26") (pinfunction "IO4_26") (pintype "bidirectional"))
    )
    (net (code "72") (name "unconnected-(U1-IO12-Pad14)") (class "Default")
      (node (ref "U1") (pin "14") (pinfunction "IO12_14") (pintype "bidirectional"))
    )
    (net (code "73") (name "unconnected-(U1-IO15-Pad23)") (class "Default")
      (node (ref "U1") (pin "23") (pinfunction "IO15_23") (pintype "bidirectional"))
    )
    (net (code "74") (name "unconnected-(U1-SCK{slash}CLK-Pad20)") (class "Default")
      (node (ref "U1") (pin "20") (pinfunction "SCK/CLK_20") (pintype "bidirectional"))
    )
    (net (code "75") (name "unconnected-(U1-SCS{slash}CMD-Pad19)") (class "Default")
      (node (ref "U1") (pin "19") (pinfunction "SCS/CMD_19") (pintype "bidirectional"))
    )
    (net (code "76") (name "unconnected-(U1-SDI{slash}SD1-Pad22)") (class "Default")
      (node (ref "U1") (pin "22") (pinfunction "SDI/SD1_22") (pintype "bidirectional"))
    )
    (net (code "77") (name "unconnected-(U1-SDO{slash}SD0-Pad21)") (class "Default")
      (node (ref "U1") (pin "21") (pinfunction "SDO/SD0_21") (pintype "bidirectional"))
    )
    (net (code "78") (name "unconnected-(U1-SHD{slash}SD2-Pad17)") (class "Default")
      (node (ref "U1") (pin "17") (pinfunction "SHD/SD2_17") (pintype "bidirectional"))
    )
    (net (code "79") (name "unconnected-(U1-SWP{slash}SD3-Pad18)") (class "Default")
      (node (ref "U1") (pin "18") (pinfunction "SWP/SD3_18") (pintype "bidirectional"))
    )
    (net (code "80") (name "unconnected-(VOC_AE-4-PadP4)") (class "Default")
      (node (ref "VOC_AE") (pin "P4") (pinfunction "4_P4") (pintype "bidirectional"))
    )
  )
)
